# SPSGRFSheet.net
KiCad netlist of a schematic drawn in Altium Designer
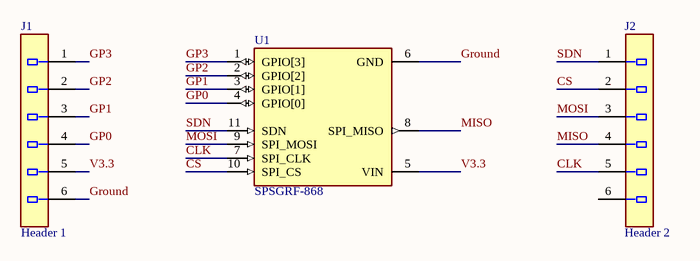
[diagram p0: SPSGRFSheet.SchDoc]

(export (version "E")
  (design (tool "Eeschema 10.0.6"))
  (components
    (comp (ref "J1")
      (value "Conn_TE_826629-6_eec")
      (footprint "TE_C-826629_0")
      (description "CONN HEADER BRKWAWAY 6POS AU")
      (fields
        (field (name "PART NUMBER") "Header 1")
        (field (name "MANUFACTURER") "TE")
        (field (name "MOUSER PART NUMBER") "571-826629-6")
      )
      (libsource (lib "") (part "Conn_TE_826629-6_eec_1"))
    )
    (comp (ref "J2")
      (value "Conn_TE_826629-6_eec")
      (footprint "TE_C-826629_0")
      (description "CONN HEADER BRKWAWAY 6POS AU")
      (fields
        (field (name "PART NUMBER") "Header 2")
        (field (name "MANUFACTURER") "TE")
        (field (name "MOUSER PART NUMBER") "571-826629-6")
      )
      (libsource (lib "Conn_TE_826629-6_eec") (part "Conn_TE_826629-6_eec"))
    )
    (comp (ref "U1")
      (value "SPSGRF-868")
      (footprint "XCVR_SPSGRF-868")
      (description "MÃ³dulo transceptor general ISM <1 GHz 868 MHz integrado, montaje en superficie de chip")
      (fields (field (name "MF") "STMicroelectronics"))
      (libsource (lib "SPSGRF-868") (part "SPSGRF-868"))
    )
  )
  (nets
    (net (code "1") (name "/CLK") (class "Default")
      (node (ref "J2") (pin "5") (pinfunction "5_5") (pintype "passive"))
      (node (ref "U1") (pin "7") (pinfunction "SPI_CLK_7") (pintype "input"))
    )
    (net (code "2") (name "/CS") (class "Default")
      (node (ref "J2") (pin "2") (pinfunction "2_2") (pintype "passive"))
      (node (ref "U1") (pin "10") (pinfunction "SPI_CS_10") (pintype "input"))
    )
    (net (code "3") (name "/GP0") (class "Default")
      (node (ref "J1") (pin "4") (pinfunction "4_4") (pintype "passive"))
      (node (ref "U1") (pin "4") (pinfunction "GPIO[0]_4") (pintype "bidirectional"))
    )
    (net (code "4") (name "/GP1") (class "Default")
      (node (ref "J1") (pin "3") (pinfunction "3_3") (pintype "passive"))
      (node (ref "U1") (pin "3") (pinfunction "GPIO[1]_3") (pintype "bidirectional"))
    )
    (net (code "5") (name "/GP2") (class "Default")
      (node (ref "J1") (pin "2") (pinfunction "2_2") (pintype "passive"))
      (node (ref "U1") (pin "2") (pinfunction "GPIO[2]_2") (pintype "bidirectional"))
    )
    (net (code "6") (name "/GP3") (class "Default")
      (node (ref "J1") (pin "1") (pinfunction "1_1") (pintype "passive"))
      (node (ref "U1") (pin "1") (pinfunction "GPIO[3]_1") (pintype "bidirectional"))
    )
    (net (code "7") (name "/Ground") (class "Default")
      (node (ref "J1") (pin "6") (pinfunction "6_6") (pintype "passive"))
      (node (ref "U1") (pin "6") (pinfunction "GND_6") (pintype "power_in"))
    )
    (net (code "8") (name "/MISO") (class "Default")
      (node (ref "J2") (pin "4") (pinfunction "4_4") (pintype "passive"))
      (node (ref "U1") (pin "8") (pinfunction "SPI_MISO_8") (pintype "output"))
    )
    (net (code "9") (name "/MOSI") (class "Default")
      (node (ref "J2") (pin "3") (pinfunction "3_3") (pintype "passive"))
      (node (ref "U1") (pin "9") (pinfunction "SPI_MOSI_9") (pintype "input"))
    )
    (net (code "10") (name "/SDN") (class "Default")
      (node (ref "J2") (pin "1") (pinfunction "1_1") (pintype "passive"))
      (node (ref "U1") (pin "11") (pinfunction "SDN_11") (pintype "input"))
    )
    (net (code "11") (name "/V3.3") (class "Default")
      (node (ref "J1") (pin "5") (pinfunction "5_5") (pintype "passive"))
      (node (ref "U1") (pin "5") (pinfunction "VIN_5") (pintype "power_in"))
    )
    (net (code "12") (name "unconnected-(J2-Pad6)") (class "Default")
      (node (ref "J2") (pin "6") (pinfunction "6_6") (pintype "passive"))
    )
  )
)
